# Adafruit_QT_Py_ESP32-S2_Rev_C.net
KiCad netlist of a schematic drawn in EAGLE
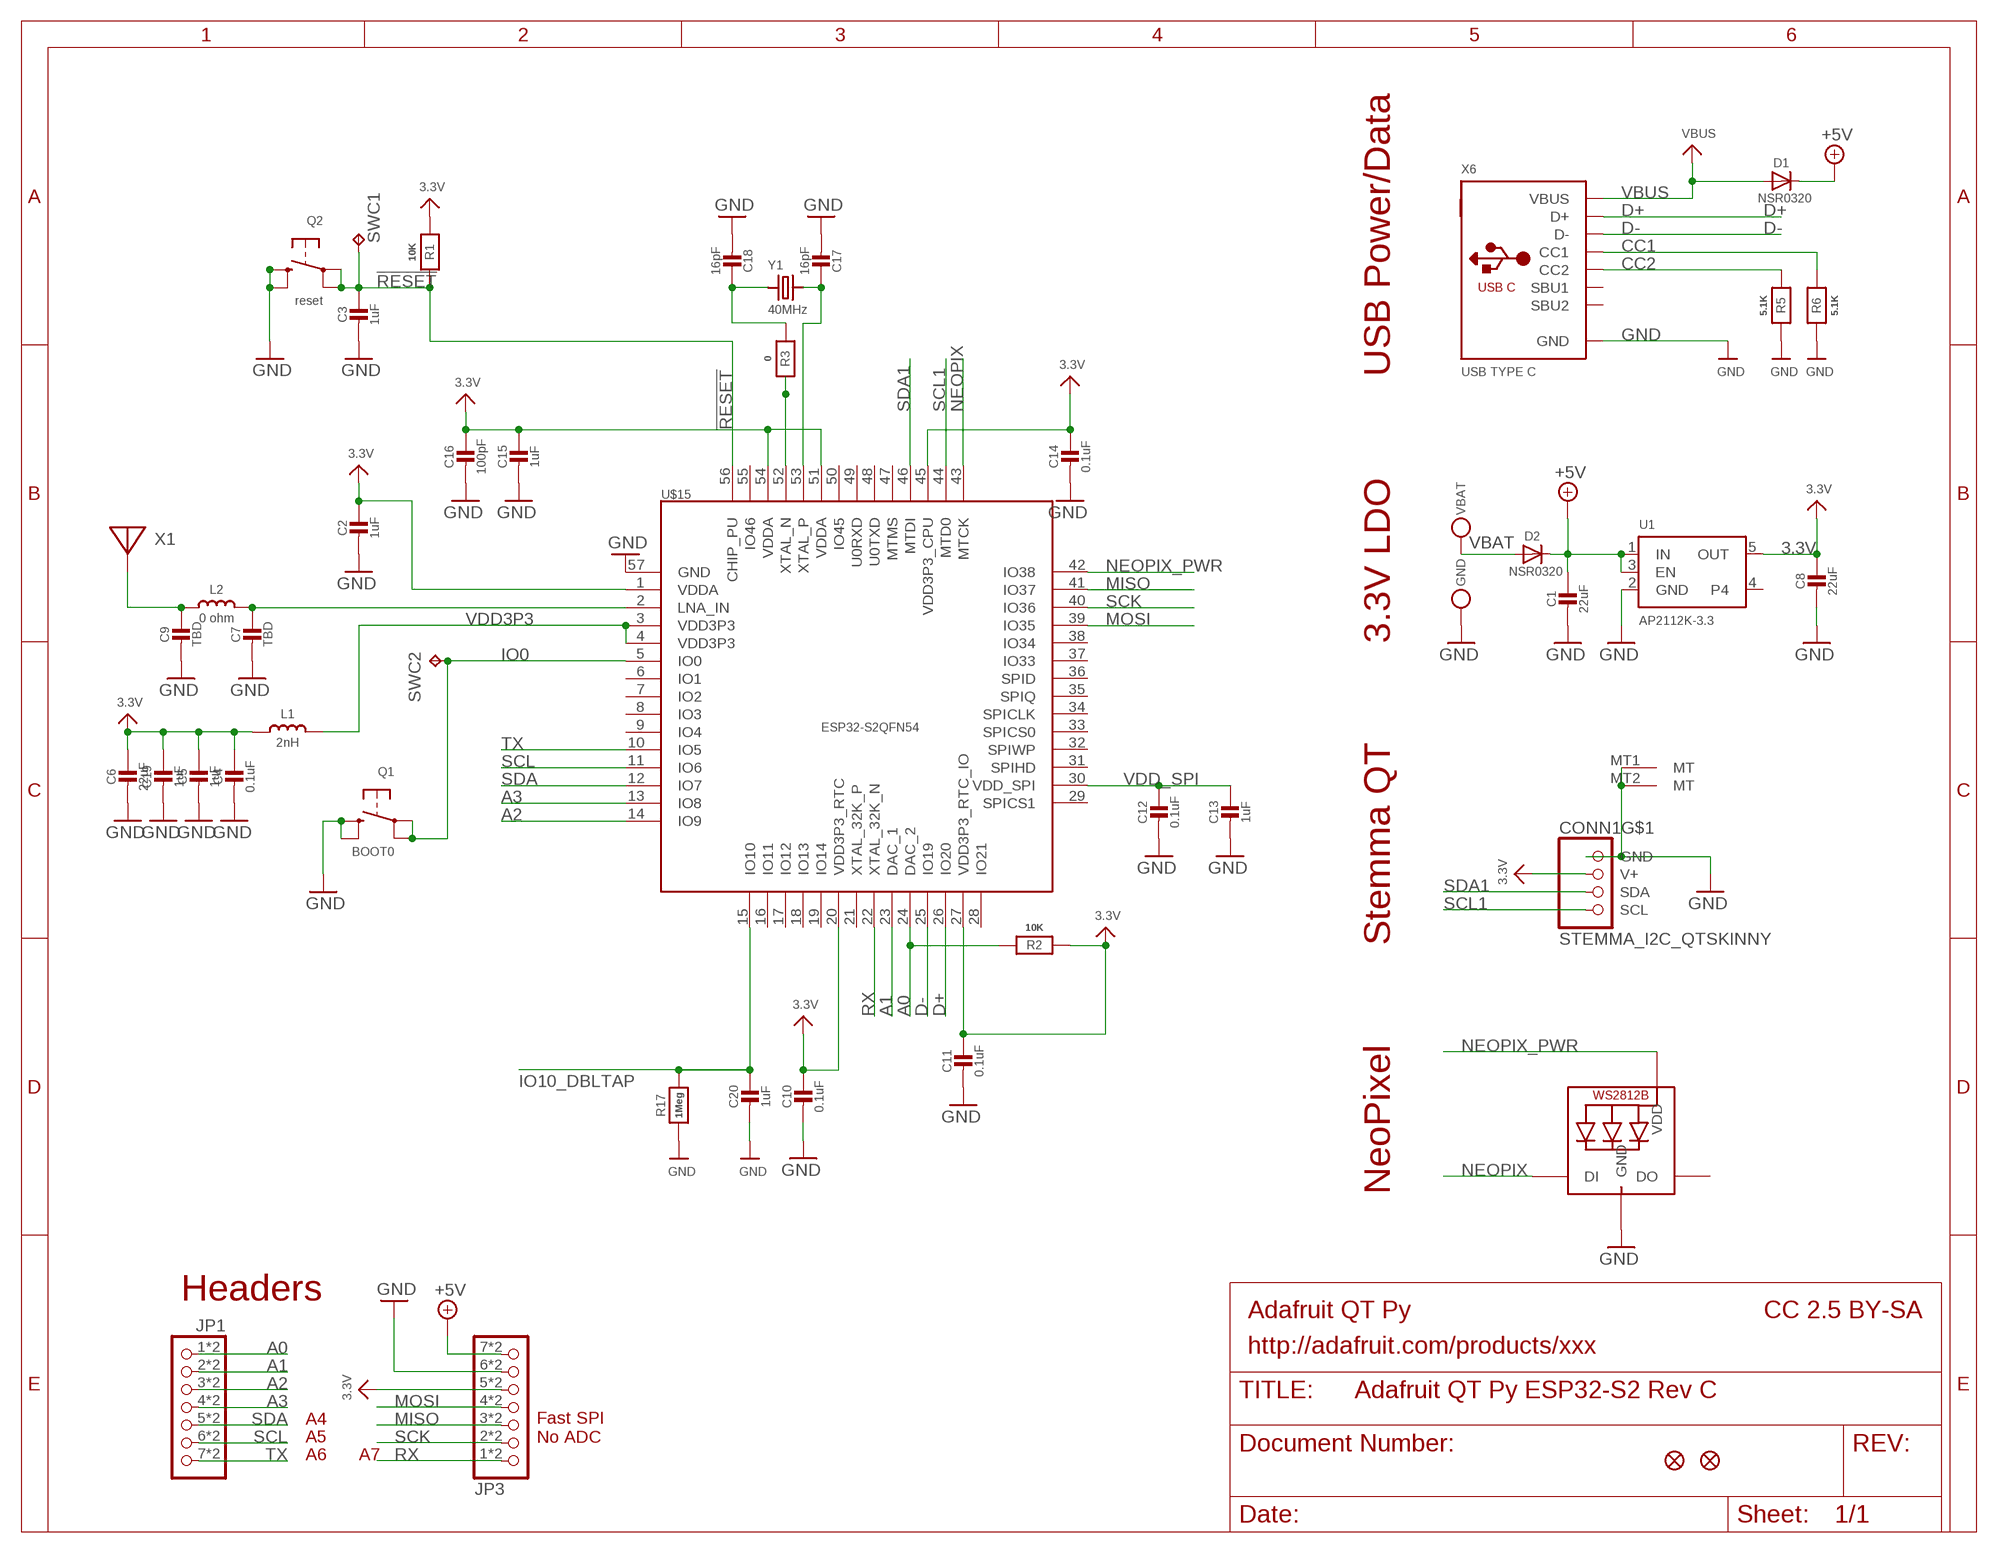
[diagram p0: schematic, sheet 1]

(export (version "E")
  (design (tool "Eeschema 10.0.6"))
  (components
    (comp (ref "C1")
      (value "22uF")
      (footprint "eagle-import:0805-NO")
      (libsource (lib "eagle-import") (part "CAP_CERAMIC0805-NOOUTLINE"))
    )
    (comp (ref "C2")
      (value "1uF")
      (footprint "eagle-import:_0402NO")
      (libsource (lib "eagle-import") (part "CAP_CERAMIC_0402NO"))
    )
    (comp (ref "C3")
      (value "1uF")
      (footprint "eagle-import:_0402NO")
      (libsource (lib "eagle-import") (part "CAP_CERAMIC_0402NO"))
    )
    (comp (ref "C4")
      (value "0.1uF")
      (footprint "eagle-import:_0402NO")
      (libsource (lib "eagle-import") (part "CAP_CERAMIC_0402NO"))
    )
    (comp (ref "C5")
      (value "1uF")
      (footprint "eagle-import:_0402NO")
      (libsource (lib "eagle-import") (part "CAP_CERAMIC_0402NO"))
    )
    (comp (ref "C6")
      (value "22uF")
      (footprint "eagle-import:0805-NO")
      (libsource (lib "eagle-import") (part "CAP_CERAMIC0805-NOOUTLINE"))
    )
    (comp (ref "C7")
      (value "TBD")
      (footprint "eagle-import:_0402NO")
      (libsource (lib "eagle-import") (part "CAP_CERAMIC_0402NO"))
    )
    (comp (ref "C8")
      (value "22uF")
      (footprint "eagle-import:0805-NO")
      (libsource (lib "eagle-import") (part "CAP_CERAMIC0805-NOOUTLINE"))
    )
    (comp (ref "C9")
      (value "TBD")
      (footprint "eagle-import:_0402NO")
      (libsource (lib "eagle-import") (part "CAP_CERAMIC_0402NO"))
    )
    (comp (ref "C10")
      (value "0.1uF")
      (footprint "eagle-import:_0402NO")
      (libsource (lib "eagle-import") (part "CAP_CERAMIC_0402NO"))
    )
    (comp (ref "C11")
      (value "0.1uF")
      (footprint "eagle-import:_0402NO")
      (libsource (lib "eagle-import") (part "CAP_CERAMIC_0402NO"))
    )
    (comp (ref "C12")
      (value "0.1uF")
      (footprint "eagle-import:_0402NO")
      (libsource (lib "eagle-import") (part "CAP_CERAMIC_0402NO"))
    )
    (comp (ref "C13")
      (value "1uF")
      (footprint "eagle-import:_0402NO")
      (libsource (lib "eagle-import") (part "CAP_CERAMIC_0402NO"))
    )
    (comp (ref "C14")
      (value "0.1uF")
      (footprint "eagle-import:_0402NO")
      (libsource (lib "eagle-import") (part "CAP_CERAMIC_0402NO"))
    )
    (comp (ref "C15")
      (value "1uF")
      (footprint "eagle-import:_0402NO")
      (libsource (lib "eagle-import") (part "CAP_CERAMIC_0402NO"))
    )
    (comp (ref "C16")
      (value "100pF")
      (footprint "eagle-import:_0402NO")
      (libsource (lib "eagle-import") (part "CAP_CERAMIC_0402NO"))
    )
    (comp (ref "C17")
      (value "16pF")
      (footprint "eagle-import:_0402NO")
      (libsource (lib "eagle-import") (part "CAP_CERAMIC_0402NO"))
    )
    (comp (ref "C18")
      (value "16pF")
      (footprint "eagle-import:_0402NO")
      (libsource (lib "eagle-import") (part "CAP_CERAMIC_0402NO"))
    )
    (comp (ref "C19")
      (value "1uF")
      (footprint "eagle-import:_0402NO")
      (libsource (lib "eagle-import") (part "CAP_CERAMIC_0402NO"))
    )
    (comp (ref "C20")
      (value "1uF")
      (footprint "eagle-import:_0402NO")
      (libsource (lib "eagle-import") (part "CAP_CERAMIC_0402NO"))
    )
    (comp (ref "CONN1")
      (value "STEMMA_I2C_QTSKINNY")
      (footprint "eagle-import:JST_SH4_SKINNY")
      (libsource (lib "eagle-import") (part "STEMMA_I2C_QTSKINNY"))
    )
    (comp (ref "D1")
      (value "NSR0320")
      (footprint "eagle-import:SOD-323_MINI")
      (libsource (lib "eagle-import") (part "DIODE_SOD323MINI"))
    )
    (comp (ref "D2")
      (value "NSR0320")
      (footprint "eagle-import:SOD-323_MINI")
      (libsource (lib "eagle-import") (part "DIODE_SOD323MINI"))
    )
    (comp (ref "GND")
      (value "TESTPOINT_MINUS")
      (footprint "eagle-import:TESTPOINT_MINUS_1X3MM")
      (libsource (lib "eagle-import") (part "TESTPOINT_MINUS"))
    )
    (comp (ref "JP1")
      (value "HEADER-1X7_CASTEL")
      (footprint "eagle-import:1X07_CASTEL")
      (libsource (lib "eagle-import") (part "HEADER-1X7_CASTEL"))
    )
    (comp (ref "JP3")
      (value "HEADER-1X7_CASTEL")
      (footprint "eagle-import:1X07_CASTEL")
      (libsource (lib "eagle-import") (part "HEADER-1X7_CASTEL"))
    )
    (comp (ref "L1")
      (value "2nH")
      (footprint "eagle-import:_0402")
      (libsource (lib "eagle-import") (part "INDUCTOR_0402"))
    )
    (comp (ref "L2")
      (value "0 ohm")
      (footprint "eagle-import:_0402")
      (libsource (lib "eagle-import") (part "INDUCTOR_0402"))
    )
    (comp (ref "LED1")
      (value "WS2812B_SK6805_1515")
      (footprint "eagle-import:SK6805_1515")
      (libsource (lib "eagle-import") (part "WS2812B_SK6805_1515"))
    )
    (comp (ref "Q1")
      (value "BOOT0")
      (footprint "eagle-import:BTN_KMR2_4.6X2.8")
      (libsource (lib "eagle-import") (part "SWITCH_TACT_SMT4.6X2.8"))
    )
    (comp (ref "Q2")
      (value "reset")
      (footprint "eagle-import:BTN_KMR2_4.6X2.8")
      (libsource (lib "eagle-import") (part "SWITCH_TACT_SMT4.6X2.8"))
    )
    (comp (ref "R1")
      (value "10K")
      (footprint "eagle-import:_0402NO")
      (libsource (lib "eagle-import") (part "RESISTOR_0402NO"))
    )
    (comp (ref "R2")
      (value "10K")
      (footprint "eagle-import:_0402NO")
      (libsource (lib "eagle-import") (part "RESISTOR_0402NO"))
    )
    (comp (ref "R3")
      (value "0")
      (footprint "eagle-import:_0402NO")
      (libsource (lib "eagle-import") (part "RESISTOR_0402NO"))
    )
    (comp (ref "R5")
      (value "5.1K")
      (footprint "eagle-import:_0402NO")
      (libsource (lib "eagle-import") (part "RESISTOR_0402NO"))
    )
    (comp (ref "R6")
      (value "5.1K")
      (footprint "eagle-import:_0402NO")
      (libsource (lib "eagle-import") (part "RESISTOR_0402NO"))
    )
    (comp (ref "R17")
      (value "1Meg")
      (footprint "eagle-import:_0402NO")
      (libsource (lib "eagle-import") (part "RESISTOR_0402NO"))
    )
    (comp (ref "SWC1")
      (value "TPB1,27")
      (footprint "eagle-import:B1,27")
      (libsource (lib "eagle-import") (part "TPB1,27"))
    )
    (comp (ref "SWC2")
      (value "TPB1,27")
      (footprint "eagle-import:B1,27")
      (libsource (lib "eagle-import") (part "TPB1,27"))
    )
    (comp (ref "U$6")
      (value "FIDUCIAL_1MM")
      (footprint "eagle-import:FIDUCIAL_1MM")
      (libsource (lib "eagle-import") (part "FIDUCIAL_1MM"))
    )
    (comp (ref "U$8")
      (value "FIDUCIAL_1MM")
      (footprint "eagle-import:FIDUCIAL_1MM")
      (libsource (lib "eagle-import") (part "FIDUCIAL_1MM"))
    )
    (comp (ref "U$15")
      (value "ESP32-S2QFN54")
      (footprint "eagle-import:QFN56_7X7")
      (fields
        (field (name "DIGI-KEY_PART_NUMBER") "1965-ESP32-S2CT-ND")
        (field (name "MF") "Espressif Systems")
        (field (name "MP") "ESP32-S2")
      )
      (libsource (lib "eagle-import") (part "ESP32-S2QFN54"))
    )
    (comp (ref "U1")
      (value "AP2112K-3.3")
      (footprint "eagle-import:SOT23-5")
      (libsource (lib "eagle-import") (part "VREG_SOT23-5"))
    )
    (comp (ref "VBAT")
      (value "TESTPOINT_PLUS13")
      (footprint "eagle-import:TESTPOINT_PLUS_1X3MM")
      (libsource (lib "eagle-import") (part "TESTPOINT_PLUS13"))
    )
    (comp (ref "X1")
      (value "ANTENNA_JOHANSON_2450AT18B100")
      (footprint "eagle-import:ANT_2450AT18B100")
      (libsource (lib "eagle-import") (part "ANTENNA_JOHANSON_2450AT18B100"))
    )
    (comp (ref "X6")
      (value "USB TYPE C")
      (footprint "eagle-import:USB_C_CUSB31-CFM2AX-01-X")
      (libsource (lib "eagle-import") (part "USB_C"))
    )
    (comp (ref "Y1")
      (value "40MHz")
      (footprint "eagle-import:CRYSTAL_2X1.6")
      (libsource (lib "eagle-import") (part "CRYSTAL_2X1.6MM"))
    )
  )
  (nets
    (net (code "1") (name "+5V") (class "Default")
      (node (ref "C1") (pin "1") (pinfunction "1_1") (pintype "passive"))
      (node (ref "D1") (pin "C") (pinfunction "C_C") (pintype "passive"))
      (node (ref "D2") (pin "C") (pinfunction "C_C") (pintype "passive"))
      (node (ref "JP3") (pin "7") (pinfunction "7_7") (pintype "passive"))
      (node (ref "JP3") (pin "7C") (pinfunction "7_7C") (pintype "passive"))
      (node (ref "U1") (pin "1") (pinfunction "IN_1") (pintype "power_in"))
      (node (ref "U1") (pin "3") (pinfunction "EN_3") (pintype "input"))
    )
    (net (code "2") (name "/A0") (class "Default")
      (node (ref "JP1") (pin "1") (pinfunction "1_1") (pintype "passive"))
      (node (ref "JP1") (pin "1C") (pinfunction "1_1C") (pintype "passive"))
      (node (ref "R2") (pin "2") (pinfunction "2_2") (pintype "passive"))
      (node (ref "U$15") (pin "24") (pinfunction "DAC_2_24") (pintype "bidirectional"))
    )
    (net (code "3") (name "/A1") (class "Default")
      (node (ref "JP1") (pin "2") (pinfunction "2_2") (pintype "passive"))
      (node (ref "JP1") (pin "2C") (pinfunction "2_2C") (pintype "passive"))
      (node (ref "U$15") (pin "23") (pinfunction "DAC_1_23") (pintype "bidirectional"))
    )
    (net (code "4") (name "/A2") (class "Default")
      (node (ref "JP1") (pin "3") (pinfunction "3_3") (pintype "passive"))
      (node (ref "JP1") (pin "3C") (pinfunction "3_3C") (pintype "passive"))
      (node (ref "U$15") (pin "14") (pinfunction "IO9_14") (pintype "bidirectional"))
    )
    (net (code "5") (name "/A3") (class "Default")
      (node (ref "JP1") (pin "4") (pinfunction "4_4") (pintype "passive"))
      (node (ref "JP1") (pin "4C") (pinfunction "4_4C") (pintype "passive"))
      (node (ref "U$15") (pin "13") (pinfunction "IO8_13") (pintype "bidirectional"))
    )
    (net (code "6") (name "/CC1") (class "Default")
      (node (ref "R6") (pin "2") (pinfunction "2_2") (pintype "passive"))
      (node (ref "X6") (pin "A5") (pinfunction "CC1_A5") (pintype "bidirectional"))
    )
    (net (code "7") (name "/CC2") (class "Default")
      (node (ref "R5") (pin "2") (pinfunction "2_2") (pintype "passive"))
      (node (ref "X6") (pin "B5") (pinfunction "CC2_B5") (pintype "bidirectional"))
    )
    (net (code "8") (name "/D+") (class "Default")
      (node (ref "U$15") (pin "26") (pinfunction "IO20_26") (pintype "bidirectional"))
      (node (ref "X6") (pin "A6") (pinfunction "D+_A6") (pintype "bidirectional"))
      (node (ref "X6") (pin "B6") (pinfunction "D+_B6") (pintype "bidirectional"))
    )
    (net (code "9") (name "/D-") (class "Default")
      (node (ref "U$15") (pin "25") (pinfunction "IO19_25") (pintype "bidirectional"))
      (node (ref "X6") (pin "A7") (pinfunction "D-_A7") (pintype "bidirectional"))
      (node (ref "X6") (pin "B7") (pinfunction "D-_B7") (pintype "bidirectional"))
    )
    (net (code "10") (name "/IO0") (class "Default")
      (node (ref "Q1") (pin "A") (pinfunction "P_A") (pintype "passive"))
      (node (ref "Q1") (pin "A'") (pinfunction "P1_A'") (pintype "passive"))
      (node (ref "SWC2") (pin "TP") (pinfunction "TP_TP") (pintype "input"))
      (node (ref "U$15") (pin "5") (pinfunction "IO0_5") (pintype "bidirectional"))
    )
    (net (code "11") (name "/IO10_DBLTAP") (class "Default")
      (node (ref "C20") (pin "1") (pinfunction "1_1") (pintype "passive"))
      (node (ref "R17") (pin "2") (pinfunction "2_2") (pintype "passive"))
      (node (ref "U$15") (pin "15") (pinfunction "IO10_15") (pintype "bidirectional"))
    )
    (net (code "12") (name "/MISO") (class "Default")
      (node (ref "JP3") (pin "3") (pinfunction "3_3") (pintype "passive"))
      (node (ref "JP3") (pin "3C") (pinfunction "3_3C") (pintype "passive"))
      (node (ref "U$15") (pin "41") (pinfunction "IO37_41") (pintype "bidirectional"))
    )
    (net (code "13") (name "/MOSI") (class "Default")
      (node (ref "JP3") (pin "4") (pinfunction "4_4") (pintype "passive"))
      (node (ref "JP3") (pin "4C") (pinfunction "4_4C") (pintype "passive"))
      (node (ref "U$15") (pin "39") (pinfunction "IO35_39") (pintype "bidirectional"))
    )
    (net (code "14") (name "/NEOPIX") (class "Default")
      (node (ref "LED1") (pin "1") (pinfunction "DI_1") (pintype "input"))
      (node (ref "U$15") (pin "43") (pinfunction "MTCK_43") (pintype "bidirectional"))
    )
    (net (code "15") (name "/NEOPIX_PWR") (class "Default")
      (node (ref "LED1") (pin "2") (pinfunction "VDD_2") (pintype "power_in"))
      (node (ref "U$15") (pin "42") (pinfunction "IO38_42") (pintype "bidirectional"))
    )
    (net (code "16") (name "/RX") (class "Default")
      (node (ref "JP3") (pin "1") (pinfunction "1_1") (pintype "passive"))
      (node (ref "JP3") (pin "1C") (pinfunction "1_1C") (pintype "passive"))
      (node (ref "U$15") (pin "22") (pinfunction "XTAL_32K_N_22") (pintype "bidirectional"))
    )
    (net (code "17") (name "/SCK") (class "Default")
      (node (ref "JP3") (pin "2") (pinfunction "2_2") (pintype "passive"))
      (node (ref "JP3") (pin "2C") (pinfunction "2_2C") (pintype "passive"))
      (node (ref "U$15") (pin "40") (pinfunction "IO36_40") (pintype "bidirectional"))
    )
    (net (code "18") (name "/SCL") (class "Default")
      (node (ref "JP1") (pin "6") (pinfunction "6_6") (pintype "passive"))
      (node (ref "JP1") (pin "6C") (pinfunction "6_6C") (pintype "passive"))
      (node (ref "U$15") (pin "11") (pinfunction "IO6_11") (pintype "bidirectional"))
    )
    (net (code "19") (name "/SCL1") (class "Default")
      (node (ref "CONN1") (pin "4") (pinfunction "SCL_4") (pintype "passive"))
      (node (ref "U$15") (pin "44") (pinfunction "MTD0_44") (pintype "bidirectional"))
    )
    (net (code "20") (name "/SDA") (class "Default")
      (node (ref "JP1") (pin "5") (pinfunction "5_5") (pintype "passive"))
      (node (ref "JP1") (pin "5C") (pinfunction "5_5C") (pintype "passive"))
      (node (ref "U$15") (pin "12") (pinfunction "IO7_12") (pintype "bidirectional"))
    )
    (net (code "21") (name "/SDA1") (class "Default")
      (node (ref "CONN1") (pin "3") (pinfunction "SDA_3") (pintype "passive"))
      (node (ref "U$15") (pin "46") (pinfunction "MTDI_46") (pintype "bidirectional"))
    )
    (net (code "22") (name "/TX") (class "Default")
      (node (ref "JP1") (pin "7") (pinfunction "7_7") (pintype "passive"))
      (node (ref "JP1") (pin "7C") (pinfunction "7_7C") (pintype "passive"))
      (node (ref "U$15") (pin "10") (pinfunction "IO5_10") (pintype "bidirectional"))
    )
    (net (code "23") (name "/VBAT") (class "Default")
      (node (ref "D2") (pin "A") (pinfunction "A_A") (pintype "passive"))
      (node (ref "VBAT") (pin "P$1") (pinfunction "P$1_P$1") (pintype "bidirectional"))
    )
    (net (code "24") (name "/VDD3P3") (class "Default")
      (node (ref "L1") (pin "2") (pinfunction "2_2") (pintype "passive"))
      (node (ref "U$15") (pin "3") (pinfunction "VDD3P3_3") (pintype "power_in"))
      (node (ref "U$15") (pin "4") (pinfunction "VDD3P3_4") (pintype "power_in"))
    )
    (net (code "25") (name "/VDD_SPI") (class "Default")
      (node (ref "C12") (pin "1") (pinfunction "1_1") (pintype "passive"))
      (node (ref "C13") (pin "1") (pinfunction "1_1") (pintype "passive"))
      (node (ref "U$15") (pin "30") (pinfunction "VDD_SPI_30") (pintype "power_in"))
    )
    (net (code "26") (name "/~{RESET}") (class "Default")
      (node (ref "C3") (pin "1") (pinfunction "1_1") (pintype "passive"))
      (node (ref "Q2") (pin "A") (pinfunction "P_A") (pintype "passive"))
      (node (ref "Q2") (pin "A'") (pinfunction "P1_A'") (pintype "passive"))
      (node (ref "R1") (pin "2") (pinfunction "2_2") (pintype "passive"))
      (node (ref "SWC1") (pin "TP") (pinfunction "TP_TP") (pintype "input"))
      (node (ref "U$15") (pin "56") (pinfunction "CHIP_PU_56") (pintype "input"))
    )
    (net (code "27") (name "3.3V") (class "Default")
      (node (ref "C10") (pin "1") (pinfunction "1_1") (pintype "passive"))
      (node (ref "C11") (pin "1") (pinfunction "1_1") (pintype "passive"))
      (node (ref "C14") (pin "1") (pinfunction "1_1") (pintype "passive"))
      (node (ref "C15") (pin "1") (pinfunction "1_1") (pintype "passive"))
      (node (ref "C16") (pin "1") (pinfunction "1_1") (pintype "passive"))
      (node (ref "C19") (pin "1") (pinfunction "1_1") (pintype "passive"))
      (node (ref "C2") (pin "1") (pinfunction "1_1") (pintype "passive"))
      (node (ref "C4") (pin "1") (pinfunction "1_1") (pintype "passive"))
      (node (ref "C5") (pin "1") (pinfunction "1_1") (pintype "passive"))
      (node (ref "C6") (pin "1") (pinfunction "1_1") (pintype "passive"))
      (node (ref "C8") (pin "1") (pinfunction "1_1") (pintype "passive"))
      (node (ref "CONN1") (pin "2") (pinfunction "V+_2") (pintype "passive"))
      (node (ref "JP3") (pin "5") (pinfunction "5_5") (pintype "passive"))
      (node (ref "JP3") (pin "5C") (pinfunction "5_5C") (pintype "passive"))
      (node (ref "L1") (pin "1") (pinfunction "1_1") (pintype "passive"))
      (node (ref "R1") (pin "1") (pinfunction "1_1") (pintype "passive"))
      (node (ref "R2") (pin "1") (pinfunction "1_1") (pintype "passive"))
      (node (ref "U$15") (pin "1") (pinfunction "VDDA_1") (pintype "power_in"))
      (node (ref "U$15") (pin "20") (pinfunction "VDD3P3_RTC_20") (pintype "power_in"))
      (node (ref "U$15") (pin "27") (pinfunction "VDD3P3_RTC_IO_27") (pintype "power_in"))
      (node (ref "U$15") (pin "45") (pinfunction "VDD3P3_CPU_45") (pintype "power_in"))
      (node (ref "U$15") (pin "51") (pinfunction "VDDA_51") (pintype "power_in"))
      (node (ref "U$15") (pin "54") (pinfunction "VDDA_54") (pintype "power_in"))
      (node (ref "U1") (pin "5") (pinfunction "OUT_5") (pintype "power_in"))
    )
    (net (code "28") (name "GND") (class "Default")
      (node (ref "C1") (pin "2") (pinfunction "2_2") (pintype "passive"))
      (node (ref "C10") (pin "2") (pinfunction "2_2") (pintype "passive"))
      (node (ref "C11") (pin "2") (pinfunction "2_2") (pintype "passive"))
      (node (ref "C12") (pin "2") (pinfunction "2_2") (pintype "passive"))
      (node (ref "C13") (pin "2") (pinfunction "2_2") (pintype "passive"))
      (node (ref "C14") (pin "2") (pinfunction "2_2") (pintype "passive"))
      (node (ref "C15") (pin "2") (pinfunction "2_2") (pintype "passive"))
      (node (ref "C16") (pin "2") (pinfunction "2_2") (pintype "passive"))
      (node (ref "C17") (pin "2") (pinfunction "2_2") (pintype "passive"))
      (node (ref "C18") (pin "2") (pinfunction "2_2") (pintype "passive"))
      (node (ref "C19") (pin "2") (pinfunction "2_2") (pintype "passive"))
      (node (ref "C2") (pin "2") (pinfunction "2_2") (pintype "passive"))
      (node (ref "C20") (pin "2") (pinfunction "2_2") (pintype "passive"))
      (node (ref "C3") (pin "2") (pinfunction "2_2") (pintype "passive"))
      (node (ref "C4") (pin "2") (pinfunction "2_2") (pintype "passive"))
      (node (ref "C5") (pin "2") (pinfunction "2_2") (pintype "passive"))
      (node (ref "C6") (pin "2") (pinfunction "2_2") (pintype "passive"))
      (node (ref "C7") (pin "2") (pinfunction "2_2") (pintype "passive"))
      (node (ref "C8") (pin "2") (pinfunction "2_2") (pintype "passive"))
      (node (ref "C9") (pin "2") (pinfunction "2_2") (pintype "passive"))
      (node (ref "CONN1") (pin "1") (pinfunction "GND_1") (pintype "passive"))
      (node (ref "CONN1") (pin "MT1") (pinfunction "MT_MT1") (pintype "bidirectional"))
      (node (ref "CONN1") (pin "MT2") (pinfunction "MT_MT2") (pintype "bidirectional"))
      (node (ref "GND") (pin "P$1") (pinfunction "P$1_P$1") (pintype "bidirectional"))
      (node (ref "JP3") (pin "6") (pinfunction "6_6") (pintype "passive"))
      (node (ref "JP3") (pin "6C") (pinfunction "6_6C") (pintype "passive"))
      (node (ref "LED1") (pin "4") (pinfunction "GND_4") (pintype "power_in"))
      (node (ref "Q1") (pin "B") (pinfunction "S_B") (pintype "passive"))
      (node (ref "Q1") (pin "B'") (pinfunction "S1_B'") (pintype "passive"))
      (node (ref "Q2") (pin "B") (pinfunction "S_B") (pintype "passive"))
      (node (ref "Q2") (pin "B'") (pinfunction "S1_B'") (pintype "passive"))
      (node (ref "R17") (pin "1") (pinfunction "1_1") (pintype "passive"))
      (node (ref "R5") (pin "1") (pinfunction "1_1") (pintype "passive"))
      (node (ref "R6") (pin "1") (pinfunction "1_1") (pintype "passive"))
      (node (ref "U$15") (pin "57") (pinfunction "GND_57") (pintype "power_in"))
      (node (ref "U1") (pin "2") (pinfunction "GND_2") (pintype "power_in"))
      (node (ref "X6") (pin "A1B12") (pinfunction "GND_A1B12") (pintype "power_in"))
      (node (ref "X6") (pin "B1A12") (pinfunction "GND_B1A12") (pintype "power_in"))
    )
    (net (code "29") (name "Net-(C18-Pad1)") (class "Default")
      (node (ref "C18") (pin "1") (pinfunction "1_1") (pintype "passive"))
      (node (ref "R3") (pin "1") (pinfunction "1_1") (pintype "passive"))
      (node (ref "Y1") (pin "1") (pinfunction "1_1") (pintype "passive"))
    )
    (net (code "30") (name "Net-(U$15-LNA_IN)") (class "Default")
      (node (ref "C7") (pin "1") (pinfunction "1_1") (pintype "passive"))
      (node (ref "L2") (pin "2") (pinfunction "2_2") (pintype "passive"))
      (node (ref "U$15") (pin "2") (pinfunction "LNA_IN_2") (pintype "bidirectional"))
    )
    (net (code "31") (name "Net-(U$15-XTAL_N)") (class "Default")
      (node (ref "R3") (pin "2") (pinfunction "2_2") (pintype "passive"))
      (node (ref "U$15") (pin "52") (pinfunction "XTAL_N_52") (pintype "bidirectional"))
    )
    (net (code "32") (name "Net-(U$15-XTAL_P)") (class "Default")
      (node (ref "C17") (pin "1") (pinfunction "1_1") (pintype "passive"))
      (node (ref "U$15") (pin "53") (pinfunction "XTAL_P_53") (pintype "bidirectional"))
      (node (ref "Y1") (pin "3") (pinfunction "2_3") (pintype "passive"))
    )
    (net (code "33") (name "Net-(X1-P$1)") (class "Default")
      (node (ref "C9") (pin "1") (pinfunction "1_1") (pintype "passive"))
      (node (ref "L2") (pin "1") (pinfunction "1_1") (pintype "passive"))
      (node (ref "X1") (pin "FP") (pinfunction "P$1_FP") (pintype "passive"))
    )
    (net (code "34") (name "VBUS") (class "Default")
      (node (ref "D1") (pin "A") (pinfunction "A_A") (pintype "passive"))
      (node (ref "X6") (pin "A4B9") (pinfunction "VBUS_A4B9") (pintype "power_in"))
      (node (ref "X6") (pin "B4A9") (pinfunction "VBUS_B4A9") (pintype "power_in"))
    )
    (net (code "35") (name "unconnected-(LED1-DO-Pad3)") (class "Default")
      (node (ref "LED1") (pin "3") (pinfunction "DO_3") (pintype "output"))
    )
    (net (code "36") (name "unconnected-(U$15-IO1-Pad6)") (class "Default")
      (node (ref "U$15") (pin "6") (pinfunction "IO1_6") (pintype "bidirectional"))
    )
    (net (code "37") (name "unconnected-(U$15-IO2-Pad7)") (class "Default")
      (node (ref "U$15") (pin "7") (pinfunction "IO2_7") (pintype "bidirectional"))
    )
    (net (code "38") (name "unconnected-(U$15-IO3-Pad8)") (class "Default")
      (node (ref "U$15") (pin "8") (pinfunction "IO3_8") (pintype "bidirectional"))
    )
    (net (code "39") (name "unconnected-(U$15-IO4-Pad9)") (class "Default")
      (node (ref "U$15") (pin "9") (pinfunction "IO4_9") (pintype "bidirectional"))
    )
    (net (code "40") (name "unconnected-(U$15-IO11-Pad16)") (class "Default")
      (node (ref "U$15") (pin "16") (pinfunction "IO11_16") (pintype "bidirectional"))
    )
    (net (code "41") (name "unconnected-(U$15-IO12-Pad17)") (class "Default")
      (node (ref "U$15") (pin "17") (pinfunction "IO12_17") (pintype "bidirectional"))
    )
    (net (code "42") (name "unconnected-(U$15-IO13-Pad18)") (class "Default")
      (node (ref "U$15") (pin "18") (pinfunction "IO13_18") (pintype "bidirectional"))
    )
    (net (code "43") (name "unconnected-(U$15-IO14-Pad19)") (class "Default")
      (node (ref "U$15") (pin "19") (pinfunction "IO14_19") (pintype "bidirectional"))
    )
    (net (code "44") (name "unconnected-(U$15-IO21-Pad28)") (class "Default")
      (node (ref "U$15") (pin "28") (pinfunction "IO21_28") (pintype "bidirectional"))
    )
    (net (code "45") (name "unconnected-(U$15-IO33-Pad37)") (class "Default")
      (node (ref "U$15") (pin "37") (pinfunction "IO33_37") (pintype "bidirectional"))
    )
    (net (code "46") (name "unconnected-(U$15-IO34-Pad38)") (class "Default")
      (node (ref "U$15") (pin "38") (pinfunction "IO34_38") (pintype "bidirectional"))
    )
    (net (code "47") (name "unconnected-(U$15-IO45-Pad50)") (class "Default")
      (node (ref "U$15") (pin "50") (pinfunction "IO45_50") (pintype "bidirectional"))
    )
    (net (code "48") (name "unconnected-(U$15-IO46-Pad55)") (class "Default")
      (node (ref "U$15") (pin "55") (pinfunction "IO46_55") (pintype "input"))
    )
    (net (code "49") (name "unconnected-(U$15-MTMS-Pad47)") (class "Default")
      (node (ref "U$15") (pin "47") (pinfunction "MTMS_47") (pintype "bidirectional"))
    )
    (net (code "50") (name "unconnected-(U$15-SPICLK-Pad34)") (class "Default")
      (node (ref "U$15") (pin "34") (pinfunction "SPICLK_34") (pintype "bidirectional"))
    )
    (net (code "51") (name "unconnected-(U$15-SPICS0-Pad33)") (class "Default")
      (node (ref "U$15") (pin "33") (pinfunction "SPICS0_33") (pintype "bidirectional"))
    )
    (net (code "52") (name "unconnected-(U$15-SPICS1-Pad29)") (class "Default")
      (node (ref "U$15") (pin "29") (pinfunction "SPICS1_29") (pintype "bidirectional"))
    )
    (net (code "53") (name "unconnected-(U$15-SPID-Pad36)") (class "Default")
      (node (ref "U$15") (pin "36") (pinfunction "SPID_36") (pintype "bidirectional"))
    )
    (net (code "54") (name "unconnected-(U$15-SPIHD-Pad31)") (class "Default")
      (node (ref "U$15") (pin "31") (pinfunction "SPIHD_31") (pintype "bidirectional"))
    )
    (net (code "55") (name "unconnected-(U$15-SPIQ-Pad35)") (class "Default")
      (node (ref "U$15") (pin "35") (pinfunction "SPIQ_35") (pintype "bidirectional"))
    )
    (net (code "56") (name "unconnected-(U$15-SPIWP-Pad32)") (class "Default")
      (node (ref "U$15") (pin "32") (pinfunction "SPIWP_32") (pintype "bidirectional"))
    )
    (net (code "57") (name "unconnected-(U$15-U0RXD-Pad49)") (class "Default")
      (node (ref "U$15") (pin "49") (pinfunction "U0RXD_49") (pintype "bidirectional"))
    )
    (net (code "58") (name "unconnected-(U$15-U0TXD-Pad48)") (class "Default")
      (node (ref "U$15") (pin "48") (pinfunction "U0TXD_48") (pintype "bidirectional"))
    )
    (net (code "59") (name "unconnected-(U$15-XTAL_32K_P-Pad21)") (class "Default")
      (node (ref "U$15") (pin "21") (pinfunction "XTAL_32K_P_21") (pintype "bidirectional"))
    )
    (net (code "60") (name "unconnected-(U1-P4-Pad4)") (class "Default")
      (node (ref "U1") (pin "4") (pinfunction "P4_4") (pintype "bidirectional"))
    )
    (net (code "61") (name "unconnected-(X6-SBU1-PadA8)") (class "Default")
      (node (ref "X6") (pin "A8") (pinfunction "SBU1_A8") (pintype "bidirectional"))
    )
    (net (code "62") (name "unconnected-(X6-SBU2-PadB8)") (class "Default")
      (node (ref "X6") (pin "B8") (pinfunction "SBU2_B8") (pintype "bidirectional"))
    )
  )
)
